# SensorBoard.net
KiCad netlist of a schematic drawn in Altium Designer
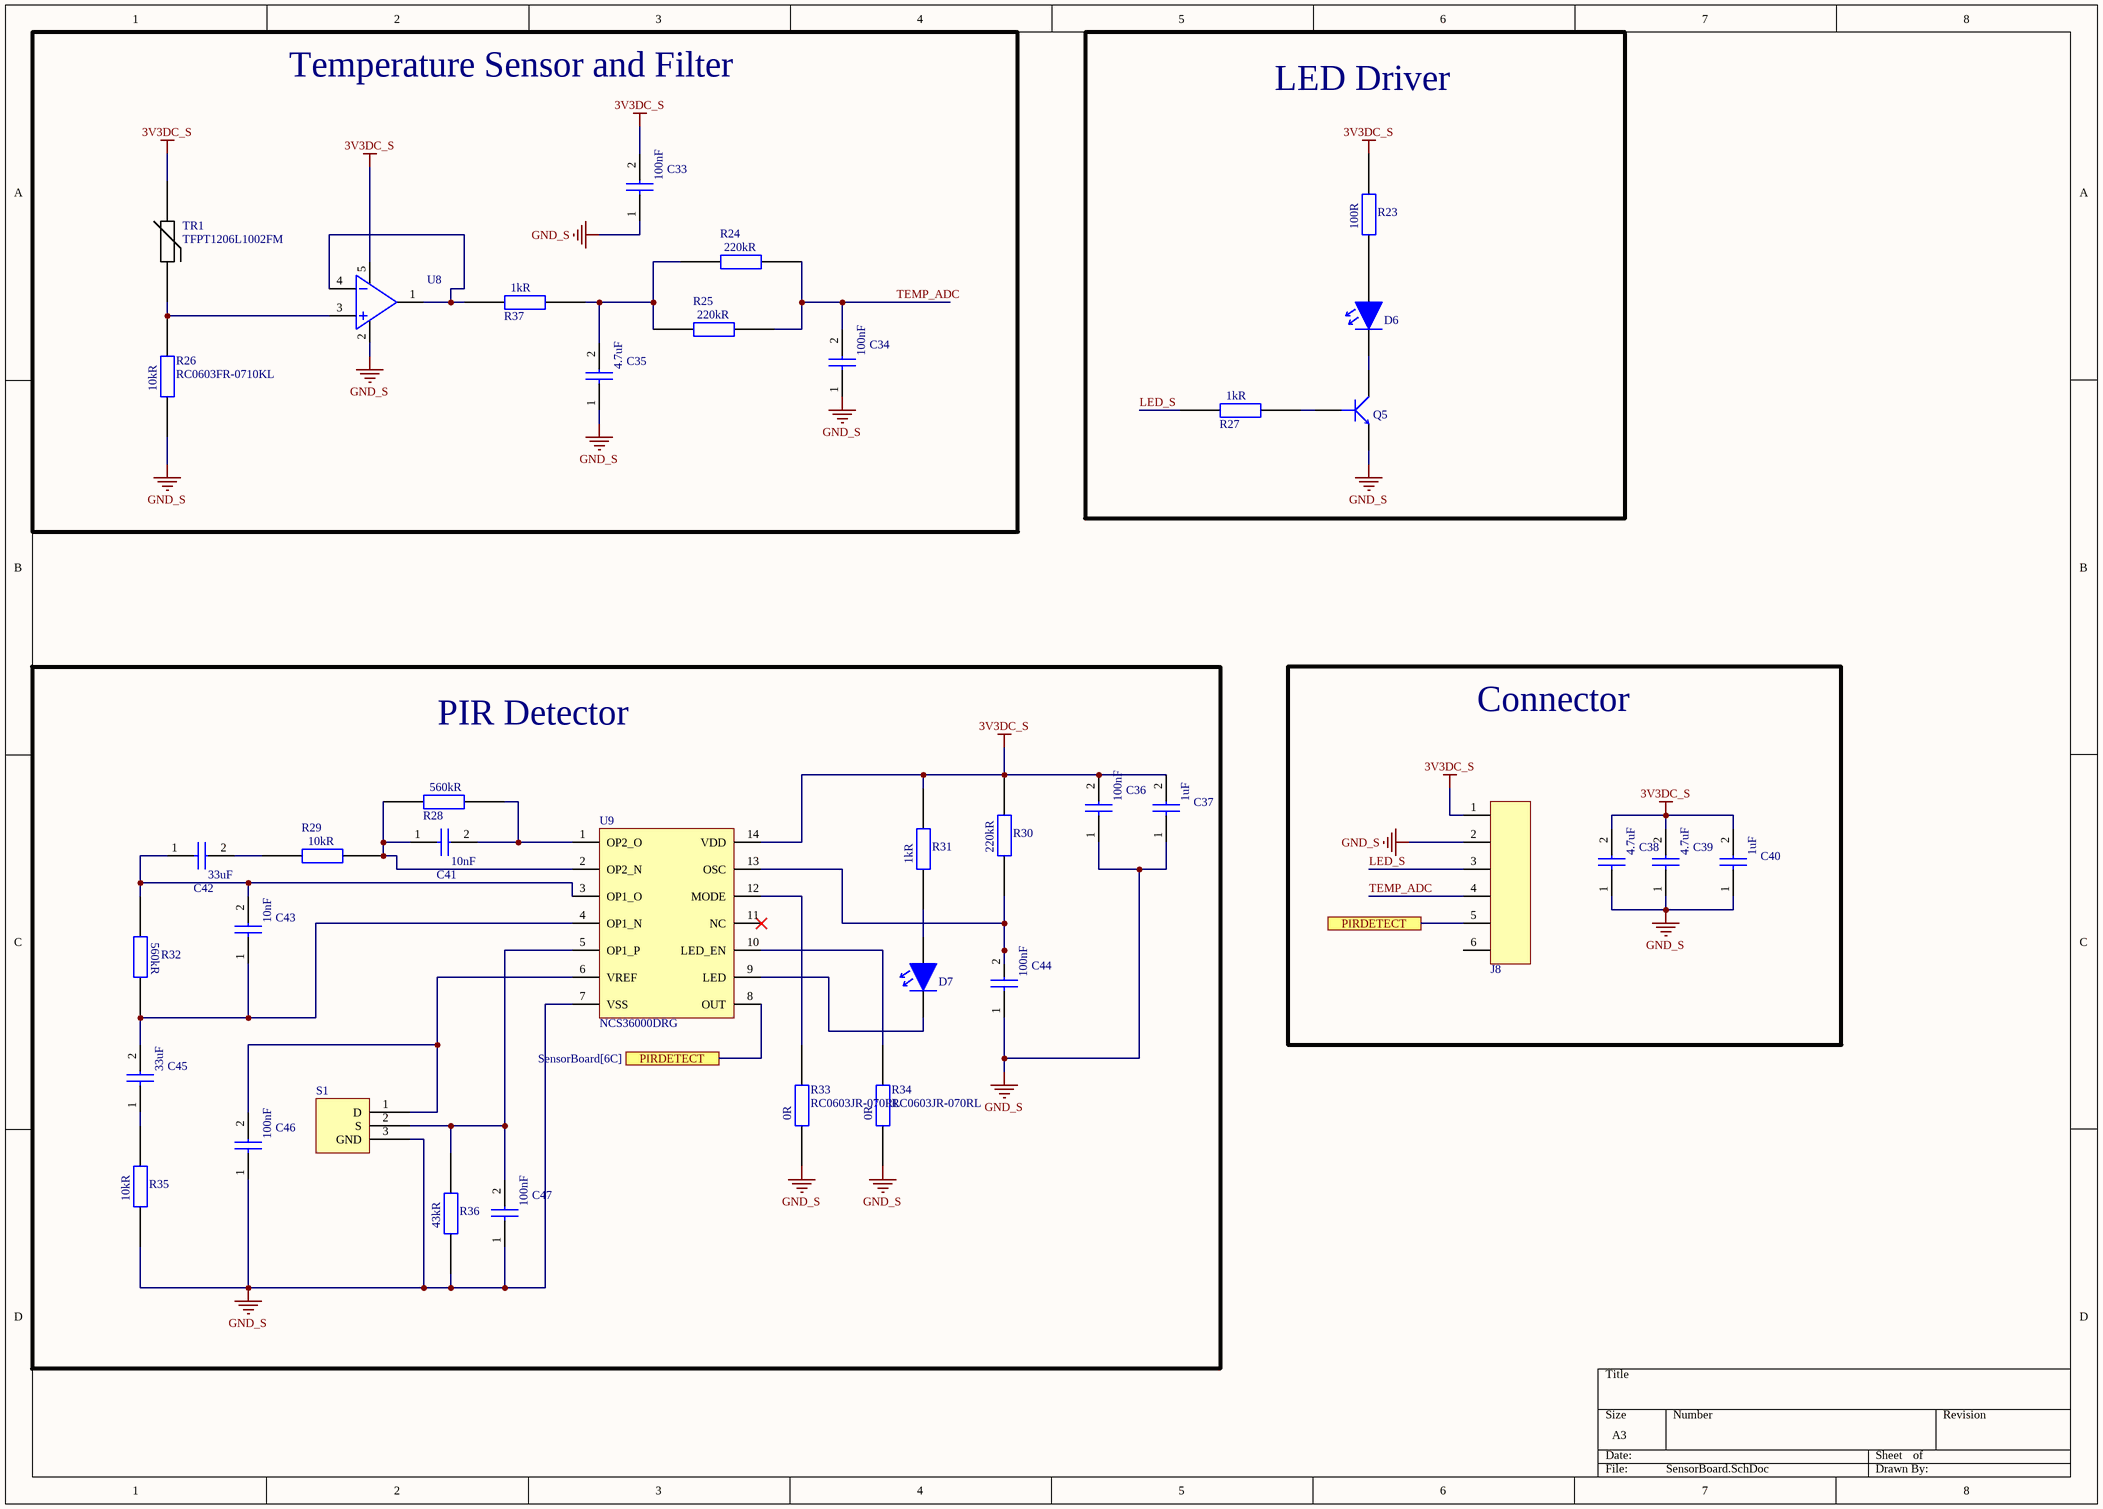
[diagram p0: SensorBoard.SchDoc]

(export (version "E")
  (design (tool "Eeschema 10.0.6"))
  (components
    (comp (ref "C33")
      (value "CL21B104KBCNNNC")
      (footprint "CAP_0805")
      (description "CAP CER 100nF %10 0603 SMD")
      (fields
        (field (name "MANUFACTURER") "Samsung")
        (field (name "TOLERANCE") "10%")
        (field (name "DESIGNED BY") "BERK")
      )
      (libsource (lib "bowtie") (part "CAP CER 0805 100nF %10"))
    )
    (comp (ref "C34")
      (value "CL21B104KBCNNNC")
      (footprint "CAP_0805")
      (description "CAP CER 100nF %10 0603 SMD")
      (fields
        (field (name "MANUFACTURER") "Samsung")
        (field (name "TOLERANCE") "10%")
        (field (name "DESIGNED BY") "BERK")
      )
      (libsource (lib "bowtie") (part "CAP CER 0805 100nF %10"))
    )
    (comp (ref "C35")
      (value "CL21A475KAQNNNE")
      (footprint "CAP_0805")
      (description "CAP CER 4.7uF %10 0805")
      (fields
        (field (name "MANUFACTURER") "Samsung")
        (field (name "TOLERANCE") "10%")
        (field (name "DESIGNED BY") "BERK")
      )
      (libsource (lib "bowtie") (part "CAP CER 0805 4.7uF %10"))
    )
    (comp (ref "C36")
      (value "CL21B104KBCNNNC")
      (footprint "CAP_0805")
      (description "CAP CER 100nF %10 0603 SMD")
      (fields
        (field (name "MANUFACTURER") "Samsung")
        (field (name "TOLERANCE") "10%")
        (field (name "DESIGNED BY") "BERK")
      )
      (libsource (lib "bowtie") (part "CAP CER 0805 100nF %10"))
    )
    (comp (ref "C37")
      (value "CL21B105KBFNNNE")
      (footprint "CAP_0805")
      (description "CAP CER 1uF %10 0805")
      (fields
        (field (name "MANUFACTURER") "Samsung")
        (field (name "TOLERANCE") "10%")
        (field (name "DESIGNED BY") "BERK")
      )
      (libsource (lib "bowtie") (part "CAP CER 0805 1uF %10"))
    )
    (comp (ref "C38")
      (value "CL21A475KAQNNNE")
      (footprint "CAP_0805")
      (description "CAP CER 4.7uF %10 0805")
      (fields
        (field (name "MANUFACTURER") "Samsung")
        (field (name "TOLERANCE") "10%")
        (field (name "DESIGNED BY") "BERK")
      )
      (libsource (lib "bowtie") (part "CAP CER 0805 4.7uF %10"))
    )
    (comp (ref "C39")
      (value "CL21A475KAQNNNE")
      (footprint "CAP_0805")
      (description "CAP CER 4.7uF %10 0805")
      (fields
        (field (name "MANUFACTURER") "Samsung")
        (field (name "TOLERANCE") "10%")
        (field (name "DESIGNED BY") "BERK")
      )
      (libsource (lib "bowtie") (part "CAP CER 0805 4.7uF %10"))
    )
    (comp (ref "C40")
      (value "CL21B105KBFNNNE")
      (footprint "CAP_0805")
      (description "CAP CER 1uF %10 0805")
      (fields
        (field (name "MANUFACTURER") "Samsung")
        (field (name "TOLERANCE") "10%")
        (field (name "DESIGNED BY") "BERK")
      )
      (libsource (lib "bowtie") (part "CAP CER 0805 1uF %10"))
    )
    (comp (ref "C41")
      (value "0603B103K160CT")
      (footprint "CAP_0603")
      (description "CAP CER 10nF %10 0603")
      (fields
        (field (name "MANUFACTURER") "Walsin Technologies")
        (field (name "TOLERANCE") "10%")
        (field (name "DESIGNED BY") "BERK")
      )
      (libsource (lib "bowtie") (part "CAP CER 0603 10nF %10"))
    )
    (comp (ref "C42")
      (value "C3216X5R1E336M160AC")
      (footprint "CAP_1206")
      (description "CAP CER 33uF %20 1206 SMD")
      (fields
        (field (name "MANUFACTURER") "TDK")
        (field (name "TOLERANCE") "20%")
        (field (name "DESIGNED BY") "BERK")
      )
      (libsource (lib "bowtie") (part "CAP CER 1206 33uF %20"))
    )
    (comp (ref "C43")
      (value "0603B103K160CT")
      (footprint "CAP_0603")
      (description "CAP CER 10nF %10 0603")
      (fields
        (field (name "MANUFACTURER") "Walsin Technologies")
        (field (name "TOLERANCE") "10%")
        (field (name "DESIGNED BY") "BERK")
      )
      (libsource (lib "bowtie") (part "CAP CER 0603 10nF %10"))
    )
    (comp (ref "C44")
      (value "CL21B104KBCNNNC")
      (footprint "CAP_0805")
      (description "CAP CER 100nF %10 0603 SMD")
      (fields
        (field (name "MANUFACTURER") "Samsung")
        (field (name "TOLERANCE") "10%")
        (field (name "DESIGNED BY") "BERK")
      )
      (libsource (lib "bowtie") (part "CAP CER 0805 100nF %10"))
    )
    (comp (ref "C45")
      (value "C3216X5R1E336M160AC")
      (footprint "CAP_1206")
      (description "CAP CER 33uF %20 1206 SMD")
      (fields
        (field (name "MANUFACTURER") "TDK")
        (field (name "TOLERANCE") "20%")
        (field (name "DESIGNED BY") "BERK")
      )
      (libsource (lib "bowtie") (part "CAP CER 1206 33uF %20"))
    )
    (comp (ref "C46")
      (value "CL21B104KBCNNNC")
      (footprint "CAP_0805")
      (description "CAP CER 100nF %10 0603 SMD")
      (fields
        (field (name "MANUFACTURER") "Samsung")
        (field (name "TOLERANCE") "10%")
        (field (name "DESIGNED BY") "BERK")
      )
      (libsource (lib "bowtie") (part "CAP CER 0805 100nF %10"))
    )
    (comp (ref "C47")
      (value "CL21B104KBCNNNC")
      (footprint "CAP_0805")
      (description "CAP CER 100nF %10 0603 SMD")
      (fields
        (field (name "MANUFACTURER") "Samsung")
        (field (name "TOLERANCE") "10%")
        (field (name "DESIGNED BY") "BERK")
      )
      (libsource (lib "bowtie") (part "CAP CER 0805 100nF %10"))
    )
    (comp (ref "D6")
      (value "LH R974-LP-1")
      (footprint "LED_RED_0805")
      (description "LED Uni-Color Hyper Red 660nm 2-Pin Chip 0805(2012Metric) T/R")
      (fields (field (name "MANUFACTURER") "Osram Opto") (field (name "DESIGNED BY") "BERK"))
      (libsource (lib "bowtie") (part "LED RED 0805"))
    )
    (comp (ref "D7")
      (value "LTST-C171GKT")
      (footprint "LED_GREEN_0805")
      (description "Green 0805 130 º Min 5 mcd Typical 12 mcd Water Clear Lens SMT LED")
      (fields (field (name "MANUFACTURER") "Vishay Lite-On") (field (name "DESIGNED BY") "BERK"))
      (libsource (lib "bowtie") (part "LED GREEN 0805"))
    )
    (comp (ref "J8")
      (value "64800611622")
      (footprint "64800611622")
      (description "1.50mm 6PIN Connector")
      (fields (field (name "MANUFACTURER") "Wurth Electronics"))
      (libsource (lib "bowtie") (part "64800611622_conn_6pin"))
    )
    (comp (ref "Q5")
      (value "MMBT3904-7-F")
      (footprint "SOT23-F")
      (description "Transistor General Purpose BJT NPN 40 Volt 0.2A Automotive 3-Pin SOT-23")
      (fields (field (name "MANUFACTURER") "Diodes Zetex") (field (name "DESIGNED BY") "BERK"))
      (libsource (lib "bowtie") (part "MMBT3904-7-F"))
    )
    (comp (ref "R23")
      (value "RC0603JR-07100RL")
      (footprint "RES_0603")
      (description "RES 100 %5 OHM 0603 SMD")
      (fields
        (field (name "MANUFACTURER") "Yageo")
        (field (name "TOLERANCE") "5%")
        (field (name "DESIGNED BY") "BERK")
      )
      (libsource (lib "bowtie") (part "RES 0603 100R %5"))
    )
    (comp (ref "R24")
      (value "RC0603JR-07220KL")
      (footprint "RES_0603")
      (description "RES 220K %5 OHM 0603 SMD")
      (fields (field (name "MANUFACTURER") "Yageo") (field (name "TOLERANCE") "5%"))
      (libsource (lib "bowtie") (part "RES 0603 220kR %5"))
    )
    (comp (ref "R25")
      (value "RC0603JR-07220KL")
      (footprint "RES_0603")
      (description "RES 220K %5 OHM 0603 SMD")
      (fields (field (name "MANUFACTURER") "Yageo") (field (name "TOLERANCE") "5%"))
      (libsource (lib "bowtie") (part "RES 0603 220kR %5"))
    )
    (comp (ref "R26")
      (value "RC0603FR-0710KL")
      (footprint "RES_0603")
      (description "RES 10K %1 OHM 0603 SMD")
      (fields (field (name "DESIGNED BY") "Mert Ali Şentürk"))
      (libsource (lib "bowtie") (part "RES 0603 10kR %1"))
    )
    (comp (ref "R27")
      (value "RC0603FR-0710KL")
      (footprint "RES_0603")
      (description "RES 1K %1 OHM 0603 SMD")
      (fields
        (field (name "MANUFACTURER") "Yageo")
        (field (name "MANUFACTURER PART NUMBER") "RC0603JR-071KL")
        (field (name "DESIGNED BY") "BERK")
      )
      (libsource (lib "bowtie") (part "RES 0603 1kR %1"))
    )
    (comp (ref "R28")
      (value "RC0603JR-07560KL")
      (footprint "RES_0603")
      (description "RES SMD 560K OHM 5% 1/10W 0603")
      (fields
        (field (name "MANUFACTURER") "Yageo")
        (field (name "TOLERANCE") "5%")
        (field (name "DESIGNED BY") "BERK")
      )
      (libsource (lib "bowtie") (part "RES 0603 560kR %5"))
    )
    (comp (ref "R29")
      (value "RC0603FR-0710KL")
      (footprint "RES_0603")
      (description "RES 10K %1 OHM 0603 SMD")
      (fields (field (name "DESIGNED BY") "Mert Ali Şentürk"))
      (libsource (lib "bowtie") (part "RES 0603 10kR %1"))
    )
    (comp (ref "R30")
      (value "RC0603JR-07220KL")
      (footprint "RES_0603")
      (description "RES 220K %5 OHM 0603 SMD")
      (fields (field (name "MANUFACTURER") "Yageo") (field (name "TOLERANCE") "5%"))
      (libsource (lib "bowtie") (part "RES 0603 220kR %5"))
    )
    (comp (ref "R31")
      (value "RC0603FR-0710KL")
      (footprint "RES_0603")
      (description "RES 1K %1 OHM 0603 SMD")
      (fields
        (field (name "MANUFACTURER") "Yageo")
        (field (name "MANUFACTURER PART NUMBER") "RC0603JR-071KL")
        (field (name "DESIGNED BY") "BERK")
      )
      (libsource (lib "bowtie") (part "RES 0603 1kR %1"))
    )
    (comp (ref "R32")
      (value "RC0603JR-07560KL")
      (footprint "RES_0603")
      (description "RES SMD 560K OHM 5% 1/10W 0603")
      (fields
        (field (name "MANUFACTURER") "Yageo")
        (field (name "TOLERANCE") "5%")
        (field (name "DESIGNED BY") "BERK")
      )
      (libsource (lib "bowtie") (part "RES 0603 560kR %5"))
    )
    (comp (ref "R33")
      (value "RC0603JR-070RL")
      (footprint "RES_0603")
      (description "RES 0 %1 OHM 0603 SMD")
      (fields (field (name "DESIGNED BY") "Mert Ali Şentürk"))
      (libsource (lib "bowtie") (part "RES 0603 0R %1"))
    )
    (comp (ref "R34")
      (value "RC0603JR-070RL")
      (footprint "RES_0603")
      (description "RES 0 %1 OHM 0603 SMD")
      (fields (field (name "DESIGNED BY") "Mert Ali Şentürk"))
      (libsource (lib "bowtie") (part "RES 0603 0R %1"))
    )
    (comp (ref "R35")
      (value "RC0603FR-0710KL")
      (footprint "RES_0603")
      (description "RES 10K %1 OHM 0603 SMD")
      (fields (field (name "DESIGNED BY") "Mert Ali Şentürk"))
      (libsource (lib "bowtie") (part "RES 0603 10kR %1"))
    )
    (comp (ref "R36")
      (value "RC0603JR-0743KL")
      (footprint "RES_0603")
      (description "RES 43K %5 OHM 0603 SMD")
      (fields
        (field (name "MANUFACTURER") "Yageo")
        (field (name "TOLERANCE") "5%")
        (field (name "DESIGNED BY") "BERK")
      )
      (libsource (lib "bowtie") (part "RES 0603 43kR %5"))
    )
    (comp (ref "R37")
      (value "RC0603FR-0710KL")
      (footprint "RES_0603")
      (description "RES 1K %1 OHM 0603 SMD")
      (fields
        (field (name "MANUFACTURER") "Yageo")
        (field (name "MANUFACTURER PART NUMBER") "RC0603JR-071KL")
        (field (name "DESIGNED BY") "BERK")
      )
      (libsource (lib "bowtie") (part "RES 0603 1kR %1"))
    )
    (comp (ref "S1")
      (value "LHI 878/3902")
      (footprint "LHI878")
      (fields (field (name "DESIGNED BY") "Mert Ali Şentürk"))
      (libsource (lib "bowtie") (part "LHI 878/3902"))
    )
    (comp (ref "TR1")
      (value "TFPT1206L1002FM")
      (footprint "RES_1206")
      (description "Thermistor PTC 10K Ohm 1% 2-Pin 1206 Surface Mount Solder Pad T/R Automotive")
      (fields
        (field (name "MANUFACTURER") "Vishay Dale")
        (field (name "TOLERANCE") "1%")
        (field (name "DESIGNED BY") "Mert Ali Şentürk")
      )
      (libsource (lib "bowtie") (part "TFPT1206L1002FM"))
    )
    (comp (ref "U8")
      (value "OPA314AIDBVR")
      (footprint "SOT23-5")
      (description "Op Amp OPA314")
      (fields (field (name "MANUFACTURER") "Texas Instruments") (field (name "DESIGNED BY") "BERK"))
      (libsource (lib "bowtie") (part "OPA314"))
    )
    (comp (ref "U9")
      (value "NCS36000DRG")
      (footprint "SOIC14")
      (description "PIR Controller Low Noise Amplifiers and LDO Regulator 14-Pin SOIC N T/R")
      (fields (field (name "MANUFACTURER") "ON Semiconductor") (field (name "DESIGNED BY") "BERK"))
      (libsource (lib "bowtie") (part "NCS36000"))
    )
  )
  (nets
    (net (code "1") (name "/LED_S") (class "Default")
      (node (ref "J8") (pin "3") (pintype "power_in"))
      (node (ref "R27") (pin "1") (pinfunction "1_1") (pintype "passive"))
    )
    (net (code "2") (name "/PIRDETECT") (class "Default")
      (node (ref "J8") (pin "5") (pintype "power_in"))
      (node (ref "U9") (pin "8") (pinfunction "OUT_8") (pintype "passive"))
    )
    (net (code "3") (name "/TEMP_ADC") (class "Default")
      (node (ref "C34") (pin "2") (pinfunction "2_2") (pintype "passive"))
      (node (ref "J8") (pin "4") (pintype "power_in"))
      (node (ref "R24") (pin "2") (pinfunction "2_2") (pintype "passive"))
      (node (ref "R25") (pin "2") (pinfunction "2_2") (pintype "passive"))
    )
    (net (code "4") (name "3V3DC_S") (class "Default")
      (node (ref "C33") (pin "2") (pinfunction "2_2") (pintype "passive"))
      (node (ref "C36") (pin "2") (pinfunction "2_2") (pintype "passive"))
      (node (ref "C37") (pin "2") (pinfunction "2_2") (pintype "passive"))
      (node (ref "C38") (pin "2") (pinfunction "2_2") (pintype "passive"))
      (node (ref "C39") (pin "2") (pinfunction "2_2") (pintype "passive"))
      (node (ref "C40") (pin "2") (pinfunction "2_2") (pintype "passive"))
      (node (ref "J8") (pin "1") (pintype "power_in"))
      (node (ref "R23") (pin "2") (pinfunction "2_2") (pintype "passive"))
      (node (ref "R30") (pin "2") (pinfunction "2_2") (pintype "passive"))
      (node (ref "R31") (pin "2") (pinfunction "2_2") (pintype "passive"))
      (node (ref "TR1") (pin "2") (pinfunction "2_2") (pintype "passive"))
      (node (ref "U8") (pin "5") (pinfunction "5_5") (pintype "passive"))
      (node (ref "U9") (pin "14") (pinfunction "VDD_14") (pintype "passive"))
    )
    (net (code "5") (name "GND_S") (class "Default")
      (node (ref "C33") (pin "1") (pinfunction "1_1") (pintype "passive"))
      (node (ref "C34") (pin "1") (pinfunction "1_1") (pintype "passive"))
      (node (ref "C35") (pin "1") (pinfunction "1_1") (pintype "passive"))
      (node (ref "C36") (pin "1") (pinfunction "1_1") (pintype "passive"))
      (node (ref "C37") (pin "1") (pinfunction "1_1") (pintype "passive"))
      (node (ref "C38") (pin "1") (pinfunction "1_1") (pintype "passive"))
      (node (ref "C39") (pin "1") (pinfunction "1_1") (pintype "passive"))
      (node (ref "C40") (pin "1") (pinfunction "1_1") (pintype "passive"))
      (node (ref "C44") (pin "1") (pinfunction "1_1") (pintype "passive"))
      (node (ref "C46") (pin "1") (pinfunction "1_1") (pintype "passive"))
      (node (ref "C47") (pin "1") (pinfunction "1_1") (pintype "passive"))
      (node (ref "J8") (pin "2") (pintype "power_in"))
      (node (ref "Q5") (pin "2") (pinfunction "E_2") (pintype "power_in"))
      (node (ref "R26") (pin "1") (pinfunction "1_1") (pintype "passive"))
      (node (ref "R33") (pin "1") (pinfunction "1_1") (pintype "passive"))
      (node (ref "R34") (pin "1") (pinfunction "1_1") (pintype "passive"))
      (node (ref "R35") (pin "1") (pinfunction "1_1") (pintype "passive"))
      (node (ref "R36") (pin "1") (pinfunction "1_1") (pintype "passive"))
      (node (ref "S1") (pin "3") (pinfunction "GND_3") (pintype "passive"))
      (node (ref "U8") (pin "2") (pinfunction "2_2") (pintype "passive"))
      (node (ref "U9") (pin "7") (pinfunction "VSS_7") (pintype "passive"))
    )
    (net (code "6") (name "Net-(C35-Pad2)") (class "Default")
      (node (ref "C35") (pin "2") (pinfunction "2_2") (pintype "passive"))
      (node (ref "R24") (pin "1") (pinfunction "1_1") (pintype "passive"))
      (node (ref "R25") (pin "1") (pinfunction "1_1") (pintype "passive"))
      (node (ref "R37") (pin "2") (pinfunction "2_2") (pintype "passive"))
    )
    (net (code "7") (name "Net-(C42-Pad2)") (class "Default")
      (node (ref "C42") (pin "2") (pinfunction "2_2") (pintype "passive"))
      (node (ref "R29") (pin "1") (pinfunction "1_1") (pintype "passive"))
    )
    (net (code "8") (name "Net-(C45-Pad1)") (class "Default")
      (node (ref "C45") (pin "1") (pinfunction "1_1") (pintype "passive"))
      (node (ref "R35") (pin "2") (pinfunction "2_2") (pintype "passive"))
    )
    (net (code "9") (name "Net-(D6-Pad2)") (class "Default")
      (node (ref "D6") (pin "2") (pinfunction "2_2") (pintype "power_in"))
      (node (ref "R23") (pin "1") (pinfunction "1_1") (pintype "passive"))
    )
    (net (code "10") (name "Net-(D7-Pad2)") (class "Default")
      (node (ref "D7") (pin "2") (pinfunction "2_2") (pintype "power_in"))
      (node (ref "R31") (pin "1") (pinfunction "1_1") (pintype "passive"))
    )
    (net (code "11") (name "Net-(Q5-B)") (class "Default")
      (node (ref "Q5") (pin "1") (pinfunction "B_1") (pintype "power_in"))
      (node (ref "R27") (pin "2") (pinfunction "2_2") (pintype "passive"))
    )
    (net (code "12") (name "Net-(Q5-C)") (class "Default")
      (node (ref "D6") (pin "1") (pinfunction "1_1") (pintype "power_in"))
      (node (ref "Q5") (pin "3") (pinfunction "C_3") (pintype "power_in"))
    )
    (net (code "13") (name "Net-(R26-Pad2)") (class "Default")
      (node (ref "R26") (pin "2") (pinfunction "2_2") (pintype "passive"))
      (node (ref "TR1") (pin "1") (pinfunction "1_1") (pintype "passive"))
      (node (ref "U8") (pin "3") (pinfunction "3_3") (pintype "passive"))
    )
    (net (code "14") (name "Net-(R37-Pad1)") (class "Default")
      (node (ref "R37") (pin "1") (pinfunction "1_1") (pintype "passive"))
      (node (ref "U8") (pin "1") (pinfunction "1_1") (pintype "passive"))
      (node (ref "U8") (pin "4") (pinfunction "4_4") (pintype "passive"))
    )
    (net (code "15") (name "Net-(S1-D)") (class "Default")
      (node (ref "C46") (pin "2") (pinfunction "2_2") (pintype "passive"))
      (node (ref "S1") (pin "1") (pinfunction "D_1") (pintype "passive"))
      (node (ref "U9") (pin "6") (pinfunction "VREF_6") (pintype "passive"))
    )
    (net (code "16") (name "Net-(S1-S)") (class "Default")
      (node (ref "C47") (pin "2") (pinfunction "2_2") (pintype "passive"))
      (node (ref "R36") (pin "2") (pinfunction "2_2") (pintype "passive"))
      (node (ref "S1") (pin "2") (pinfunction "S_2") (pintype "passive"))
      (node (ref "U9") (pin "5") (pinfunction "OP1_P_5") (pintype "passive"))
    )
    (net (code "17") (name "Net-(U9-LED)") (class "Default")
      (node (ref "D7") (pin "1") (pinfunction "1_1") (pintype "power_in"))
      (node (ref "U9") (pin "9") (pinfunction "LED_9") (pintype "passive"))
    )
    (net (code "18") (name "Net-(U9-LED_EN)") (class "Default")
      (node (ref "R34") (pin "2") (pinfunction "2_2") (pintype "passive"))
      (node (ref "U9") (pin "10") (pinfunction "LED_EN_10") (pintype "passive"))
    )
    (net (code "19") (name "Net-(U9-MODE)") (class "Default")
      (node (ref "R33") (pin "2") (pinfunction "2_2") (pintype "passive"))
      (node (ref "U9") (pin "12") (pinfunction "MODE_12") (pintype "passive"))
    )
    (net (code "20") (name "Net-(U9-OP1_N)") (class "Default")
      (node (ref "C43") (pin "1") (pinfunction "1_1") (pintype "passive"))
      (node (ref "C45") (pin "2") (pinfunction "2_2") (pintype "passive"))
      (node (ref "R32") (pin "2") (pinfunction "2_2") (pintype "passive"))
      (node (ref "U9") (pin "4") (pinfunction "OP1_N_4") (pintype "passive"))
    )
    (net (code "21") (name "Net-(U9-OP1_O)") (class "Default")
      (node (ref "C42") (pin "1") (pinfunction "1_1") (pintype "passive"))
      (node (ref "C43") (pin "2") (pinfunction "2_2") (pintype "passive"))
      (node (ref "R32") (pin "1") (pinfunction "1_1") (pintype "passive"))
      (node (ref "U9") (pin "3") (pinfunction "OP1_O_3") (pintype "passive"))
    )
    (net (code "22") (name "Net-(U9-OP2_N)") (class "Default")
      (node (ref "C41") (pin "1") (pinfunction "1_1") (pintype "passive"))
      (node (ref "R28") (pin "1") (pinfunction "1_1") (pintype "passive"))
      (node (ref "R29") (pin "2") (pinfunction "2_2") (pintype "passive"))
      (node (ref "U9") (pin "2") (pinfunction "OP2_N_2") (pintype "passive"))
    )
    (net (code "23") (name "Net-(U9-OP2_O)") (class "Default")
      (node (ref "C41") (pin "2") (pinfunction "2_2") (pintype "passive"))
      (node (ref "R28") (pin "2") (pinfunction "2_2") (pintype "passive"))
      (node (ref "U9") (pin "1") (pinfunction "OP2_O_1") (pintype "passive"))
    )
    (net (code "24") (name "Net-(U9-OSC)") (class "Default")
      (node (ref "C44") (pin "2") (pinfunction "2_2") (pintype "passive"))
      (node (ref "R30") (pin "1") (pinfunction "1_1") (pintype "passive"))
      (node (ref "U9") (pin "13") (pinfunction "OSC_13") (pintype "passive"))
    )
    (net (code "25") (name "unconnected-(J8-Pad6)") (class "Default")
      (node (ref "J8") (pin "6") (pintype "power_in"))
    )
    (net (code "26") (name "unconnected-(U9-NC-Pad11)") (class "Default")
      (node (ref "U9") (pin "11") (pinfunction "NC_11") (pintype "passive+no_connect"))
    )
  )
)
